# ApoBoard_2017_V0_3.net
KiCad netlist of a schematic drawn in EAGLE
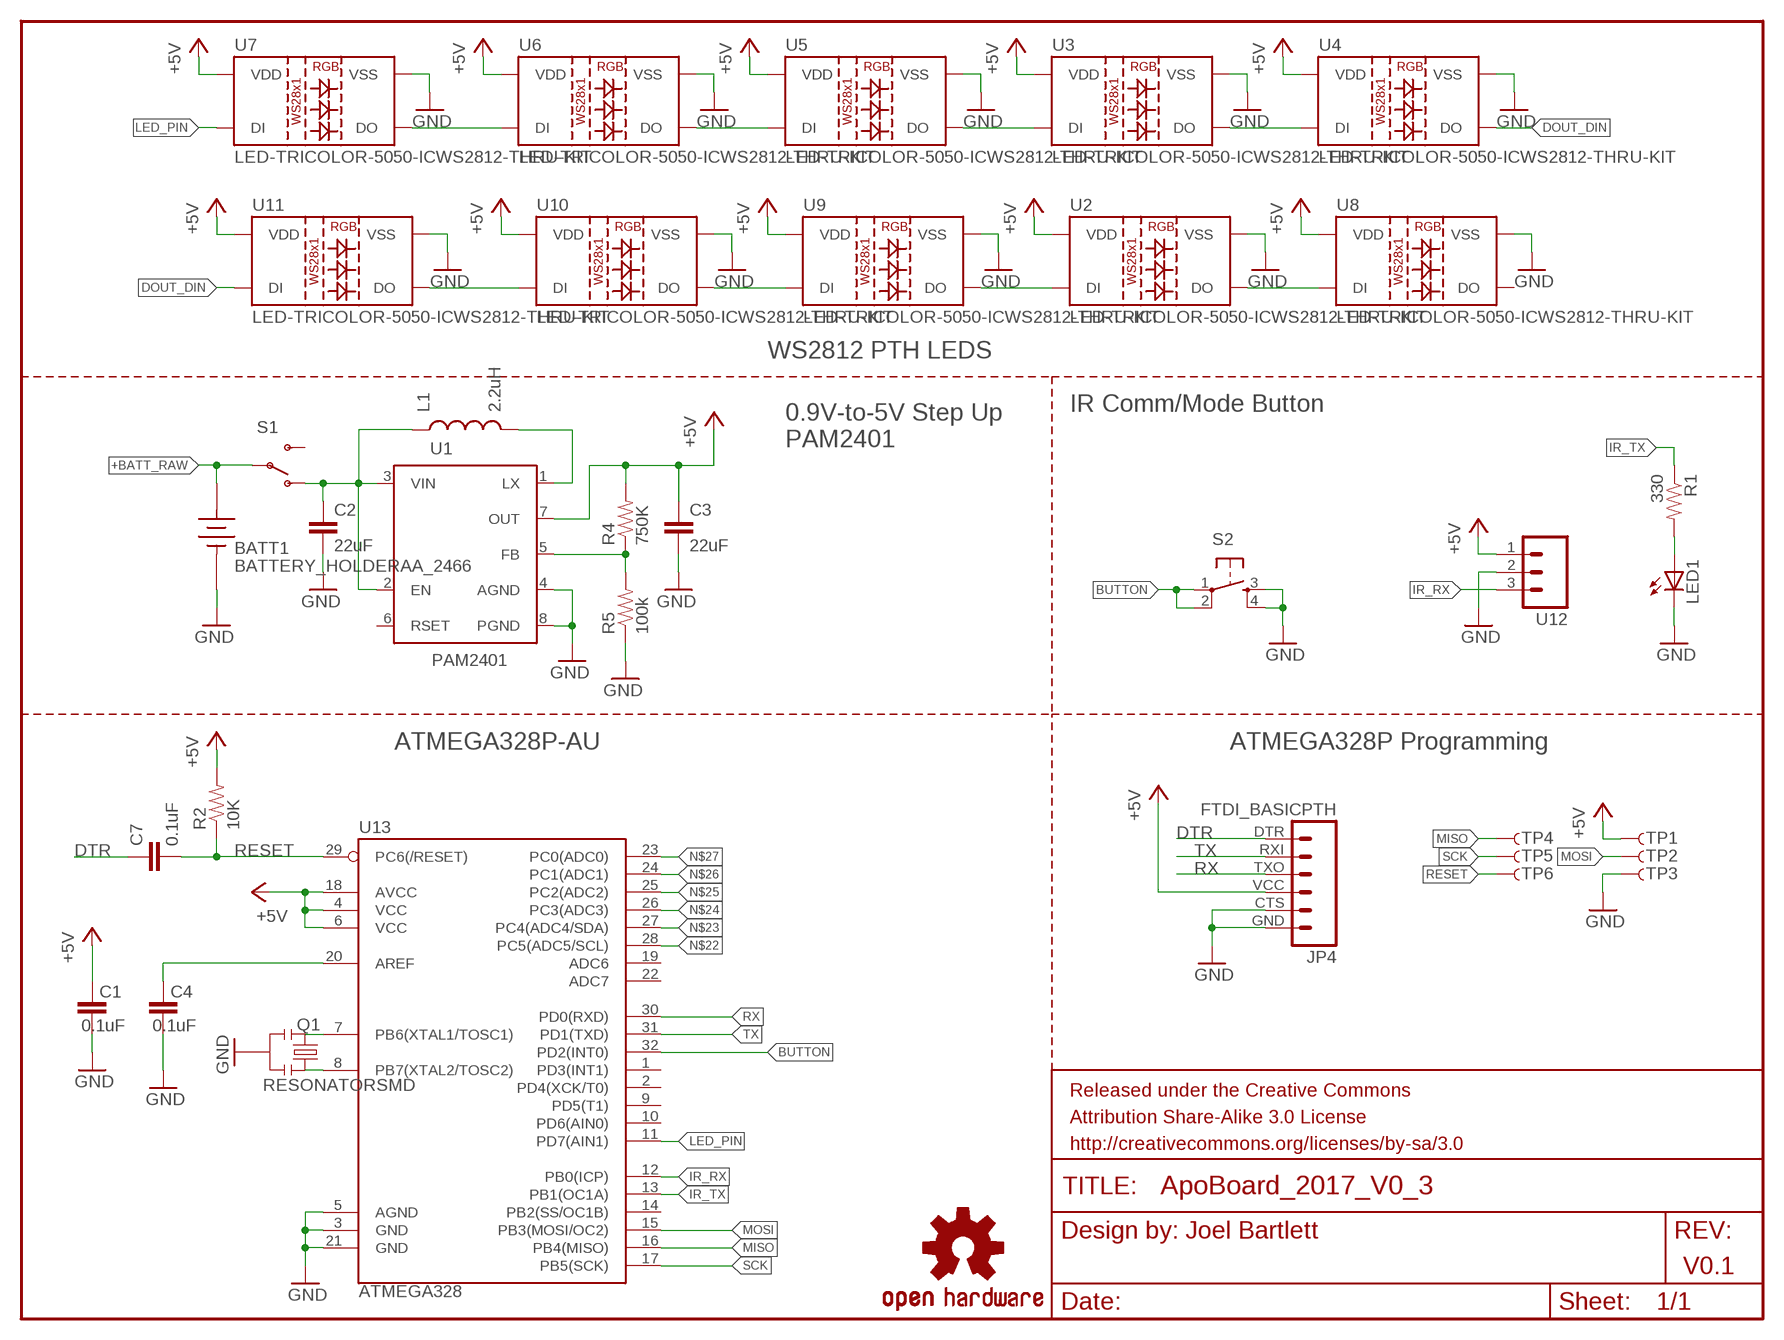
[diagram p0: schematic, sheet 1]

(export (version "E")
  (design (tool "Eeschema 10.0.6"))
  (components
    (comp (ref "BATT1")
      (value "BATTERY_HOLDERAA_2466")
      (footprint "eagle-import:BATT_HOLDER_AA_2466")
      (libsource (lib "eagle-import") (part "BATTERY_HOLDERAA_2466"))
    )
    (comp (ref "C1")
      (value "0.1uF")
      (footprint "eagle-import:0402-CAP")
      (libsource (lib "eagle-import") (part "CAP0402-CAP"))
    )
    (comp (ref "C2")
      (value "22uF")
      (footprint "eagle-import:0805")
      (libsource (lib "eagle-import") (part "22UF-6.3V-20%(0805)"))
    )
    (comp (ref "C3")
      (value "22uF")
      (footprint "eagle-import:0805")
      (libsource (lib "eagle-import") (part "22UF-6.3V-20%(0805)"))
    )
    (comp (ref "C4")
      (value "0.1uF")
      (footprint "eagle-import:0402-CAP")
      (libsource (lib "eagle-import") (part "CAP0402-CAP"))
    )
    (comp (ref "C7")
      (value "0.1uF")
      (footprint "eagle-import:0402-CAP")
      (libsource (lib "eagle-import") (part "CAP0402-CAP"))
    )
    (comp (ref "FRAME1")
      (value "FRAME-LETTER")
      (footprint "eagle-import:CREATIVE_COMMONS")
      (libsource (lib "eagle-import") (part "FRAME-LETTER"))
    )
    (comp (ref "JP4")
      (value "FTDI_BASICPTH")
      (footprint "eagle-import:FTDI_BASIC")
      (libsource (lib "eagle-import") (part "FTDI_BASICPTH"))
    )
    (comp (ref "L1")
      (value "2.2uH")
      (footprint "eagle-import:CDRH2D09")
      (libsource (lib "eagle-import") (part "INDUCTOR."))
    )
    (comp (ref "LED1")
      (value "LED5MM-KIT")
      (footprint "eagle-import:LED5MM-KIT")
      (libsource (lib "eagle-import") (part "LED5MM-KIT"))
    )
    (comp (ref "LOGO1")
      (value "OSHW-LOGOS")
      (footprint "eagle-import:OSHW-LOGO-S")
      (libsource (lib "eagle-import") (part "OSHW-LOGOS"))
    )
    (comp (ref "Q1")
      (value "RESONATORSMD")
      (footprint "eagle-import:RESONATOR-SMD")
      (libsource (lib "eagle-import") (part "RESONATORSMD"))
    )
    (comp (ref "R1")
      (value "330")
      (footprint "eagle-import:AXIAL-0.3-KIT")
      (libsource (lib "eagle-import") (part "SparkFun-Resistors_RESISTORKIT"))
    )
    (comp (ref "R2")
      (value "10K")
      (footprint "eagle-import:0402-RES")
      (libsource (lib "eagle-import") (part "RESISTOR0402-RES"))
    )
    (comp (ref "R4")
      (value "750K")
      (footprint "eagle-import:0603-RES")
      (libsource (lib "eagle-import") (part "10K-1%RES-00824"))
    )
    (comp (ref "R5")
      (value "100k")
      (footprint "eagle-import:0603-RES")
      (libsource (lib "eagle-import") (part "10K-1%RES-00824"))
    )
    (comp (ref "S1")
      (value "SWITCH-SPSTKIT")
      (footprint "eagle-import:SWITCH-SPDT_KIT")
      (libsource (lib "eagle-import") (part "SWITCH-SPSTKIT"))
    )
    (comp (ref "S2")
      (value "TAC_SWITCHPTH")
      (footprint "eagle-import:TACTILE-PTH")
      (libsource (lib "eagle-import") (part "TAC_SWITCHPTH"))
    )
    (comp (ref "TP1")
      (value "TP-3x5")
      (footprint "eagle-import:PAD.03X.05")
      (libsource (lib "eagle-import") (part "TEST-POINT3X5"))
    )
    (comp (ref "TP2")
      (value "TP-3x5")
      (footprint "eagle-import:PAD.03X.05")
      (libsource (lib "eagle-import") (part "TEST-POINT3X5"))
    )
    (comp (ref "TP3")
      (value "TP-3x5")
      (footprint "eagle-import:PAD.03X.05")
      (libsource (lib "eagle-import") (part "TEST-POINT3X5"))
    )
    (comp (ref "TP4")
      (value "TP-3x5")
      (footprint "eagle-import:PAD.03X.05")
      (libsource (lib "eagle-import") (part "TEST-POINT3X5"))
    )
    (comp (ref "TP5")
      (value "TP-3x5")
      (footprint "eagle-import:PAD.03X.05")
      (libsource (lib "eagle-import") (part "TEST-POINT3X5"))
    )
    (comp (ref "TP6")
      (value "TP-3x5")
      (footprint "eagle-import:PAD.03X.05")
      (libsource (lib "eagle-import") (part "TEST-POINT3X5"))
    )
    (comp (ref "U1")
      (value "PAM2401")
      (footprint "eagle-import:MSOP8")
      (libsource (lib "eagle-import") (part "PAM2401"))
    )
    (comp (ref "U2")
      (value "LED-TRICOLOR-5050-ICWS2812-THRU-KIT")
      (footprint "eagle-import:LED-RGB-THRU-KIT")
      (libsource (lib "eagle-import") (part "LED-TRICOLOR-5050-ICWS2812-THRU-KIT"))
    )
    (comp (ref "U3")
      (value "LED-TRICOLOR-5050-ICWS2812-THRU-KIT")
      (footprint "eagle-import:LED-RGB-THRU-KIT")
      (libsource (lib "eagle-import") (part "LED-TRICOLOR-5050-ICWS2812-THRU-KIT"))
    )
    (comp (ref "U4")
      (value "LED-TRICOLOR-5050-ICWS2812-THRU-KIT")
      (footprint "eagle-import:LED-RGB-THRU-KIT")
      (libsource (lib "eagle-import") (part "LED-TRICOLOR-5050-ICWS2812-THRU-KIT"))
    )
    (comp (ref "U5")
      (value "LED-TRICOLOR-5050-ICWS2812-THRU-KIT")
      (footprint "eagle-import:LED-RGB-THRU-KIT")
      (libsource (lib "eagle-import") (part "LED-TRICOLOR-5050-ICWS2812-THRU-KIT"))
    )
    (comp (ref "U6")
      (value "LED-TRICOLOR-5050-ICWS2812-THRU-KIT")
      (footprint "eagle-import:LED-RGB-THRU-KIT")
      (libsource (lib "eagle-import") (part "LED-TRICOLOR-5050-ICWS2812-THRU-KIT"))
    )
    (comp (ref "U7")
      (value "LED-TRICOLOR-5050-ICWS2812-THRU-KIT")
      (footprint "eagle-import:LED-RGB-THRU-KIT")
      (libsource (lib "eagle-import") (part "LED-TRICOLOR-5050-ICWS2812-THRU-KIT"))
    )
    (comp (ref "U8")
      (value "LED-TRICOLOR-5050-ICWS2812-THRU-KIT")
      (footprint "eagle-import:LED-RGB-THRU-KIT")
      (libsource (lib "eagle-import") (part "LED-TRICOLOR-5050-ICWS2812-THRU-KIT"))
    )
    (comp (ref "U9")
      (value "LED-TRICOLOR-5050-ICWS2812-THRU-KIT")
      (footprint "eagle-import:LED-RGB-THRU-KIT")
      (libsource (lib "eagle-import") (part "LED-TRICOLOR-5050-ICWS2812-THRU-KIT"))
    )
    (comp (ref "U10")
      (value "LED-TRICOLOR-5050-ICWS2812-THRU-KIT")
      (footprint "eagle-import:LED-RGB-THRU-KIT")
      (libsource (lib "eagle-import") (part "LED-TRICOLOR-5050-ICWS2812-THRU-KIT"))
    )
    (comp (ref "U11")
      (value "LED-TRICOLOR-5050-ICWS2812-THRU-KIT")
      (footprint "eagle-import:LED-RGB-THRU-KIT")
      (libsource (lib "eagle-import") (part "LED-TRICOLOR-5050-ICWS2812-THRU-KIT"))
    )
    (comp (ref "U12")
      (value "M03IR_RECEIVER")
      (footprint "eagle-import:1X03_IR_RECEIVER")
      (libsource (lib "eagle-import") (part "M03IR_RECEIVER"))
    )
    (comp (ref "U13")
      (value "ATMEGA328")
      (footprint "eagle-import:TQFP32-08")
      (libsource (lib "eagle-import") (part "ATMEGA168"))
    )
  )
  (nets
    (net (code "1") (name "+5V") (class "Default")
      (node (ref "C1") (pin "2") (pinfunction "2_2") (pintype "passive"))
      (node (ref "C3") (pin "1") (pinfunction "1_1") (pintype "passive"))
      (node (ref "JP4") (pin "VCC") (pinfunction "4_VCC") (pintype "passive"))
      (node (ref "R2") (pin "2") (pinfunction "2_2") (pintype "passive"))
      (node (ref "R4") (pin "2") (pinfunction "2_2") (pintype "passive"))
      (node (ref "TP1") (pin "P$1") (pinfunction "1_P$1") (pintype "bidirectional"))
      (node (ref "U1") (pin "7") (pinfunction "OUT_7") (pintype "bidirectional"))
      (node (ref "U10") (pin "2") (pinfunction "VDD_2") (pintype "bidirectional"))
      (node (ref "U11") (pin "2") (pinfunction "VDD_2") (pintype "bidirectional"))
      (node (ref "U12") (pin "1") (pinfunction "1_1") (pintype "passive"))
      (node (ref "U13") (pin "18") (pinfunction "AVCC_18") (pintype "bidirectional"))
      (node (ref "U13") (pin "4") (pinfunction "VCC_4") (pintype "bidirectional"))
      (node (ref "U13") (pin "6") (pinfunction "VCC_6") (pintype "bidirectional"))
      (node (ref "U2") (pin "2") (pinfunction "VDD_2") (pintype "bidirectional"))
      (node (ref "U3") (pin "2") (pinfunction "VDD_2") (pintype "bidirectional"))
      (node (ref "U4") (pin "2") (pinfunction "VDD_2") (pintype "bidirectional"))
      (node (ref "U5") (pin "2") (pinfunction "VDD_2") (pintype "bidirectional"))
      (node (ref "U6") (pin "2") (pinfunction "VDD_2") (pintype "bidirectional"))
      (node (ref "U7") (pin "2") (pinfunction "VDD_2") (pintype "bidirectional"))
      (node (ref "U8") (pin "2") (pinfunction "VDD_2") (pintype "bidirectional"))
      (node (ref "U9") (pin "2") (pinfunction "VDD_2") (pintype "bidirectional"))
    )
    (net (code "2") (name "+BATT_RAW") (class "Default")
      (node (ref "BATT1") (pin "P") (pinfunction "P_P") (pintype "bidirectional"))
      (node (ref "S1") (pin "2") (pinfunction "P_2") (pintype "passive"))
    )
    (net (code "3") (name "/DTR") (class "Default")
      (node (ref "C7") (pin "1") (pinfunction "1_1") (pintype "passive"))
      (node (ref "JP4") (pin "DTR") (pinfunction "1_DTR") (pintype "passive"))
    )
    (net (code "4") (name "BUTTON") (class "Default")
      (node (ref "S2") (pin "1") (pinfunction "1_1") (pintype "passive"))
      (node (ref "S2") (pin "2") (pinfunction "2_2") (pintype "passive"))
      (node (ref "U13") (pin "32") (pinfunction "PD2(INT0)_32") (pintype "bidirectional"))
    )
    (net (code "5") (name "DOUT_DIN") (class "Default")
      (node (ref "U11") (pin "1") (pinfunction "DI_1") (pintype "bidirectional"))
      (node (ref "U4") (pin "4") (pinfunction "DO_4") (pintype "bidirectional"))
    )
    (net (code "6") (name "GND") (class "Default")
      (node (ref "BATT1") (pin "N") (pinfunction "N_N") (pintype "bidirectional"))
      (node (ref "C1") (pin "1") (pinfunction "1_1") (pintype "passive"))
      (node (ref "C2") (pin "2") (pinfunction "2_2") (pintype "passive"))
      (node (ref "C3") (pin "2") (pinfunction "2_2") (pintype "passive"))
      (node (ref "C4") (pin "1") (pinfunction "1_1") (pintype "passive"))
      (node (ref "JP4") (pin "CTS") (pinfunction "5_CTS") (pintype "passive"))
      (node (ref "JP4") (pin "GND") (pinfunction "6_GND") (pintype "passive"))
      (node (ref "LED1") (pin "K") (pinfunction "C_K") (pintype "passive"))
      (node (ref "Q1") (pin "2") (pinfunction "2_2") (pintype "passive"))
      (node (ref "R5") (pin "1") (pinfunction "1_1") (pintype "passive"))
      (node (ref "S2") (pin "3") (pinfunction "3_3") (pintype "passive"))
      (node (ref "S2") (pin "4") (pinfunction "4_4") (pintype "passive"))
      (node (ref "TP3") (pin "P$1") (pinfunction "1_P$1") (pintype "bidirectional"))
      (node (ref "U1") (pin "4") (pinfunction "AGND_4") (pintype "bidirectional"))
      (node (ref "U1") (pin "8") (pinfunction "PGND_8") (pintype "bidirectional"))
      (node (ref "U10") (pin "3") (pinfunction "VSS_3") (pintype "bidirectional"))
      (node (ref "U11") (pin "3") (pinfunction "VSS_3") (pintype "bidirectional"))
      (node (ref "U12") (pin "2") (pinfunction "2_2") (pintype "passive"))
      (node (ref "U13") (pin "21") (pinfunction "GND_21") (pintype "bidirectional"))
      (node (ref "U13") (pin "3") (pinfunction "GND_3") (pintype "bidirectional"))
      (node (ref "U13") (pin "5") (pinfunction "AGND_5") (pintype "bidirectional"))
      (node (ref "U2") (pin "3") (pinfunction "VSS_3") (pintype "bidirectional"))
      (node (ref "U3") (pin "3") (pinfunction "VSS_3") (pintype "bidirectional"))
      (node (ref "U4") (pin "3") (pinfunction "VSS_3") (pintype "bidirectional"))
      (node (ref "U5") (pin "3") (pinfunction "VSS_3") (pintype "bidirectional"))
      (node (ref "U6") (pin "3") (pinfunction "VSS_3") (pintype "bidirectional"))
      (node (ref "U7") (pin "3") (pinfunction "VSS_3") (pintype "bidirectional"))
      (node (ref "U8") (pin "3") (pinfunction "VSS_3") (pintype "bidirectional"))
      (node (ref "U9") (pin "3") (pinfunction "VSS_3") (pintype "bidirectional"))
    )
    (net (code "7") (name "IR_RX") (class "Default")
      (node (ref "U12") (pin "3") (pinfunction "3_3") (pintype "passive"))
      (node (ref "U13") (pin "12") (pinfunction "PB0(ICP)_12") (pintype "bidirectional"))
    )
    (net (code "8") (name "IR_TX") (class "Default")
      (node (ref "R1") (pin "P$1") (pinfunction "1_P$1") (pintype "passive"))
      (node (ref "U13") (pin "13") (pinfunction "PB1(OC1A)_13") (pintype "bidirectional"))
    )
    (net (code "9") (name "LED_PIN") (class "Default")
      (node (ref "U13") (pin "11") (pinfunction "PD7(AIN1)_11") (pintype "bidirectional"))
      (node (ref "U7") (pin "1") (pinfunction "DI_1") (pintype "bidirectional"))
    )
    (net (code "10") (name "MISO") (class "Default")
      (node (ref "TP4") (pin "P$1") (pinfunction "1_P$1") (pintype "bidirectional"))
      (node (ref "U13") (pin "16") (pinfunction "PB4(MISO)_16") (pintype "bidirectional"))
    )
    (net (code "11") (name "MOSI") (class "Default")
      (node (ref "TP2") (pin "P$1") (pinfunction "1_P$1") (pintype "bidirectional"))
      (node (ref "U13") (pin "15") (pinfunction "PB3(MOSI/OC2)_15") (pintype "bidirectional"))
    )
    (net (code "12") (name "N$22") (class "Default")
      (node (ref "U13") (pin "28") (pinfunction "PC5(ADC5/SCL)_28") (pintype "bidirectional"))
    )
    (net (code "13") (name "N$23") (class "Default")
      (node (ref "U13") (pin "27") (pinfunction "PC4(ADC4/SDA)_27") (pintype "bidirectional"))
    )
    (net (code "14") (name "N$24") (class "Default")
      (node (ref "U13") (pin "26") (pinfunction "PC3(ADC3)_26") (pintype "bidirectional"))
    )
    (net (code "15") (name "N$25") (class "Default")
      (node (ref "U13") (pin "25") (pinfunction "PC2(ADC2)_25") (pintype "bidirectional"))
    )
    (net (code "16") (name "N$26") (class "Default")
      (node (ref "U13") (pin "24") (pinfunction "PC1(ADC1)_24") (pintype "bidirectional"))
    )
    (net (code "17") (name "N$27") (class "Default")
      (node (ref "U13") (pin "23") (pinfunction "PC0(ADC0)_23") (pintype "bidirectional"))
    )
    (net (code "18") (name "Net-(L1-1)") (class "Default")
      (node (ref "C2") (pin "1") (pinfunction "1_1") (pintype "passive"))
      (node (ref "L1") (pin "P$1") (pinfunction "1_P$1") (pintype "passive"))
      (node (ref "S1") (pin "1") (pinfunction "O_1") (pintype "passive"))
      (node (ref "U1") (pin "2") (pinfunction "EN_2") (pintype "bidirectional"))
      (node (ref "U1") (pin "3") (pinfunction "VIN_3") (pintype "bidirectional"))
    )
    (net (code "19") (name "Net-(L1-2)") (class "Default")
      (node (ref "L1") (pin "P$2") (pinfunction "2_P$2") (pintype "passive"))
      (node (ref "U1") (pin "1") (pinfunction "LX_1") (pintype "bidirectional"))
    )
    (net (code "20") (name "Net-(R1-2)") (class "Default")
      (node (ref "LED1") (pin "A") (pinfunction "A_A") (pintype "passive"))
      (node (ref "R1") (pin "P$2") (pinfunction "2_P$2") (pintype "passive"))
    )
    (net (code "21") (name "Net-(U1-FB)") (class "Default")
      (node (ref "R4") (pin "1") (pinfunction "1_1") (pintype "passive"))
      (node (ref "R5") (pin "2") (pinfunction "2_2") (pintype "passive"))
      (node (ref "U1") (pin "5") (pinfunction "FB_5") (pintype "bidirectional"))
    )
    (net (code "22") (name "Net-(U2-DI)") (class "Default")
      (node (ref "U2") (pin "1") (pinfunction "DI_1") (pintype "bidirectional"))
      (node (ref "U9") (pin "4") (pinfunction "DO_4") (pintype "bidirectional"))
    )
    (net (code "23") (name "Net-(U2-DO)") (class "Default")
      (node (ref "U2") (pin "4") (pinfunction "DO_4") (pintype "bidirectional"))
      (node (ref "U8") (pin "1") (pinfunction "DI_1") (pintype "bidirectional"))
    )
    (net (code "24") (name "Net-(U3-DI)") (class "Default")
      (node (ref "U3") (pin "1") (pinfunction "DI_1") (pintype "bidirectional"))
      (node (ref "U5") (pin "4") (pinfunction "DO_4") (pintype "bidirectional"))
    )
    (net (code "25") (name "Net-(U3-DO)") (class "Default")
      (node (ref "U3") (pin "4") (pinfunction "DO_4") (pintype "bidirectional"))
      (node (ref "U4") (pin "1") (pinfunction "DI_1") (pintype "bidirectional"))
    )
    (net (code "26") (name "Net-(U5-DI)") (class "Default")
      (node (ref "U5") (pin "1") (pinfunction "DI_1") (pintype "bidirectional"))
      (node (ref "U6") (pin "4") (pinfunction "DO_4") (pintype "bidirectional"))
    )
    (net (code "27") (name "Net-(U6-DI)") (class "Default")
      (node (ref "U6") (pin "1") (pinfunction "DI_1") (pintype "bidirectional"))
      (node (ref "U7") (pin "4") (pinfunction "DO_4") (pintype "bidirectional"))
    )
    (net (code "28") (name "Net-(U10-DI)") (class "Default")
      (node (ref "U10") (pin "1") (pinfunction "DI_1") (pintype "bidirectional"))
      (node (ref "U11") (pin "4") (pinfunction "DO_4") (pintype "bidirectional"))
    )
    (net (code "29") (name "Net-(U10-DO)") (class "Default")
      (node (ref "U10") (pin "4") (pinfunction "DO_4") (pintype "bidirectional"))
      (node (ref "U9") (pin "1") (pinfunction "DI_1") (pintype "bidirectional"))
    )
    (net (code "30") (name "Net-(U13-AREF)") (class "Default")
      (node (ref "C4") (pin "2") (pinfunction "2_2") (pintype "passive"))
      (node (ref "U13") (pin "20") (pinfunction "AREF_20") (pintype "bidirectional"))
    )
    (net (code "31") (name "Net-(U13-PB6(XTAL1{slash}TOSC1))") (class "Default")
      (node (ref "Q1") (pin "3") (pinfunction "3_3") (pintype "passive"))
      (node (ref "U13") (pin "7") (pinfunction "PB6(XTAL1/TOSC1)_7") (pintype "bidirectional"))
    )
    (net (code "32") (name "Net-(U13-PB7(XTAL2{slash}TOSC2))") (class "Default")
      (node (ref "Q1") (pin "1") (pinfunction "1_1") (pintype "passive"))
      (node (ref "U13") (pin "8") (pinfunction "PB7(XTAL2/TOSC2)_8") (pintype "bidirectional"))
    )
    (net (code "33") (name "RESET") (class "Default")
      (node (ref "C7") (pin "2") (pinfunction "2_2") (pintype "passive"))
      (node (ref "R2") (pin "1") (pinfunction "1_1") (pintype "passive"))
      (node (ref "TP6") (pin "P$1") (pinfunction "1_P$1") (pintype "bidirectional"))
      (node (ref "U13") (pin "29") (pinfunction "PC6(/RESET)_29") (pintype "bidirectional"))
    )
    (net (code "34") (name "RX") (class "Default")
      (node (ref "JP4") (pin "TXO") (pinfunction "3_TXO") (pintype "passive"))
      (node (ref "U13") (pin "30") (pinfunction "PD0(RXD)_30") (pintype "bidirectional"))
    )
    (net (code "35") (name "SCK") (class "Default")
      (node (ref "TP5") (pin "P$1") (pinfunction "1_P$1") (pintype "bidirectional"))
      (node (ref "U13") (pin "17") (pinfunction "PB5(SCK)_17") (pintype "bidirectional"))
    )
    (net (code "36") (name "TX") (class "Default")
      (node (ref "JP4") (pin "RXI") (pinfunction "2_RXI") (pintype "passive"))
      (node (ref "U13") (pin "31") (pinfunction "PD1(TXD)_31") (pintype "bidirectional"))
    )
    (net (code "37") (name "unconnected-(S1-S-Pad3)") (class "Default")
      (node (ref "S1") (pin "3") (pinfunction "S_3") (pintype "passive"))
    )
    (net (code "38") (name "unconnected-(U1-RSET-Pad6)") (class "Default")
      (node (ref "U1") (pin "6") (pinfunction "RSET_6") (pintype "bidirectional"))
    )
    (net (code "39") (name "unconnected-(U8-DO-Pad4)") (class "Default")
      (node (ref "U8") (pin "4") (pinfunction "DO_4") (pintype "bidirectional"))
    )
    (net (code "40") (name "unconnected-(U13-ADC6-Pad19)") (class "Default")
      (node (ref "U13") (pin "19") (pinfunction "ADC6_19") (pintype "bidirectional"))
    )
    (net (code "41") (name "unconnected-(U13-ADC7-Pad22)") (class "Default")
      (node (ref "U13") (pin "22") (pinfunction "ADC7_22") (pintype "bidirectional"))
    )
    (net (code "42") (name "unconnected-(U13-PB2(SS{slash}OC1B)-Pad14)") (class "Default")
      (node (ref "U13") (pin "14") (pinfunction "PB2(SS/OC1B)_14") (pintype "bidirectional"))
    )
    (net (code "43") (name "unconnected-(U13-PD3(INT1)-Pad1)") (class "Default")
      (node (ref "U13") (pin "1") (pinfunction "PD3(INT1)_1") (pintype "bidirectional"))
    )
    (net (code "44") (name "unconnected-(U13-PD4(XCK{slash}T0)-Pad2)") (class "Default")
      (node (ref "U13") (pin "2") (pinfunction "PD4(XCK/T0)_2") (pintype "bidirectional"))
    )
    (net (code "45") (name "unconnected-(U13-PD5(T1)-Pad9)") (class "Default")
      (node (ref "U13") (pin "9") (pinfunction "PD5(T1)_9") (pintype "bidirectional"))
    )
    (net (code "46") (name "unconnected-(U13-PD6(AIN0)-Pad10)") (class "Default")
      (node (ref "U13") (pin "10") (pinfunction "PD6(AIN0)_10") (pintype "bidirectional"))
    )
  )
)
